# FloppyController_dsPIC.net
KiCad netlist of a schematic drawn in EAGLE
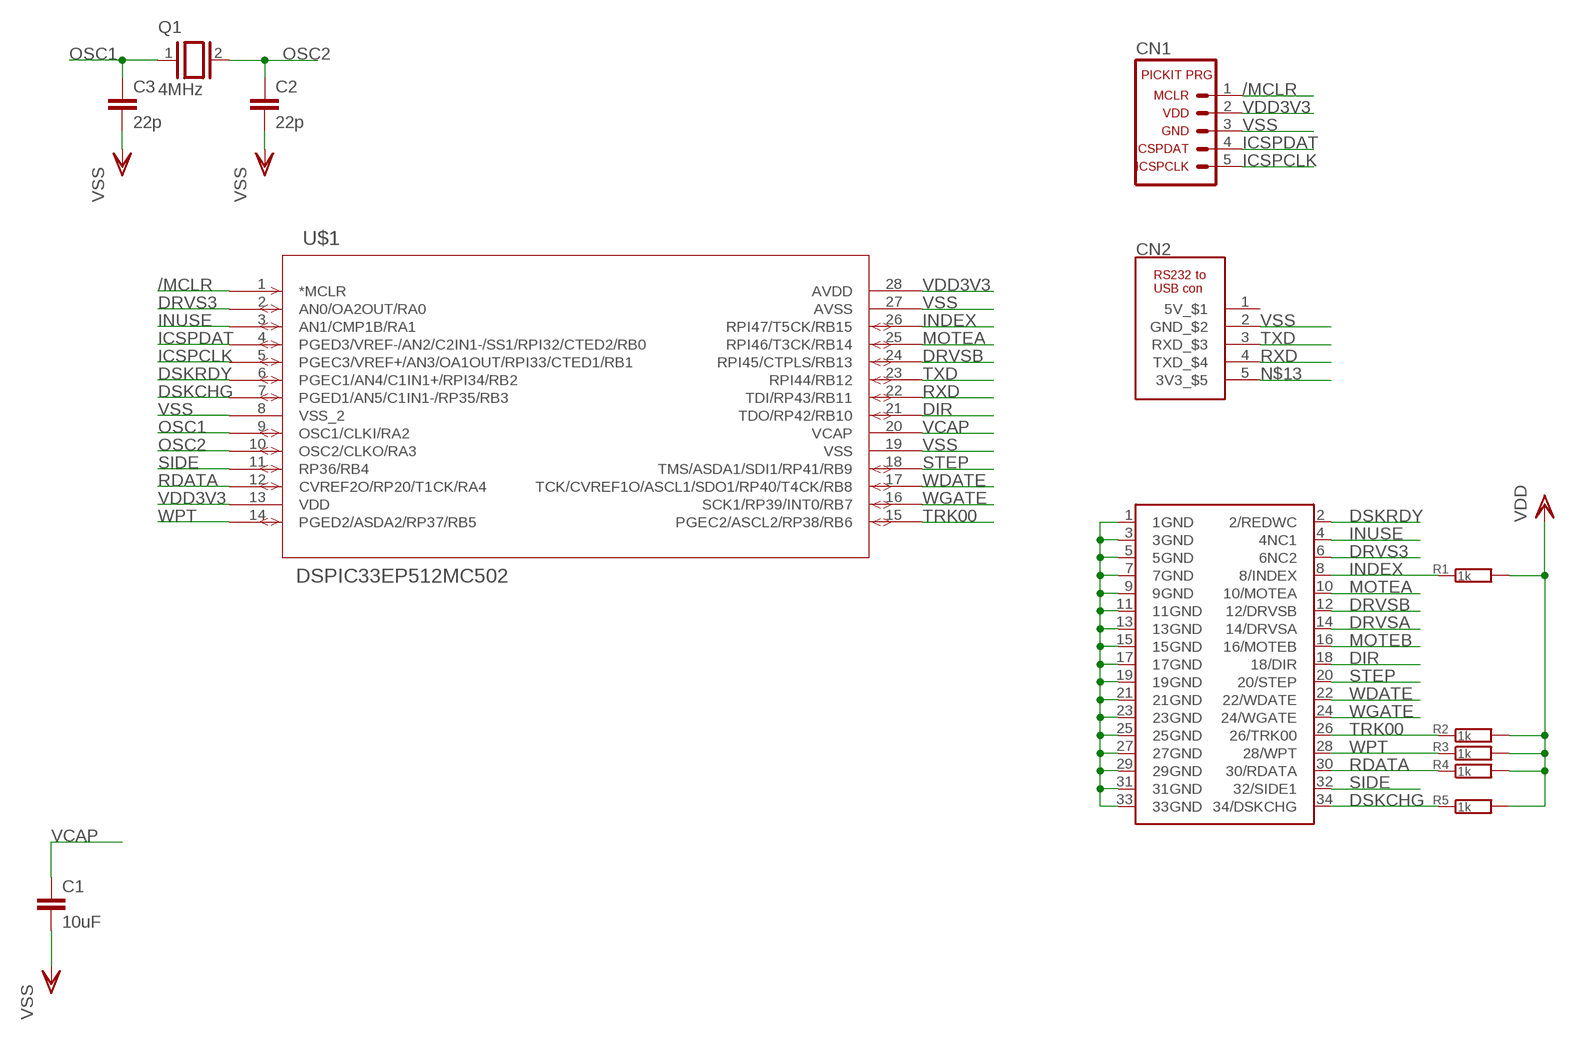
[diagram p0: schematic, sheet 1]

(export (version "E")
  (design (tool "Eeschema 10.0.6"))
  (components
    (comp (ref "C1")
      (value "10uF")
      (footprint "eagle-import:C0805TOP")
      (libsource (lib "eagle-import") (part "C-EUC0805BOTTOM"))
    )
    (comp (ref "C2")
      (value "22p")
      (footprint "eagle-import:C0603")
      (libsource (lib "eagle-import") (part "C-EUC0603"))
    )
    (comp (ref "C3")
      (value "22p")
      (footprint "eagle-import:C0603")
      (libsource (lib "eagle-import") (part "C-EUC0603"))
    )
    (comp (ref "CN1")
      (value "PICKIT3CONNECTOR")
      (footprint "eagle-import:05P")
      (libsource (lib "eagle-import") (part "PICKIT3CONNECTOR"))
    )
    (comp (ref "CN2")
      (value "RS232_TO_USB_CONNECTOR")
      (footprint "eagle-import:05P")
      (libsource (lib "eagle-import") (part "RS232_TO_USB_CONNECTOR"))
    )
    (comp (ref "Q1")
      (value "4MHz")
      (footprint "eagle-import:QS")
      (libsource (lib "eagle-import") (part "XTAL/S"))
    )
    (comp (ref "R1")
      (value "1k")
      (footprint "eagle-import:M1206")
      (libsource (lib "eagle-import") (part "R-EU_M1206BOTTOM"))
    )
    (comp (ref "R2")
      (value "1k")
      (footprint "eagle-import:M1206")
      (libsource (lib "eagle-import") (part "R-EU_M1206BOTTOM"))
    )
    (comp (ref "R3")
      (value "1k")
      (footprint "eagle-import:M1206")
      (libsource (lib "eagle-import") (part "R-EU_M1206BOTTOM"))
    )
    (comp (ref "R4")
      (value "1k")
      (footprint "eagle-import:M1206")
      (libsource (lib "eagle-import") (part "R-EU_M1206BOTTOM"))
    )
    (comp (ref "R5")
      (value "1k")
      (footprint "eagle-import:M1206")
      (libsource (lib "eagle-import") (part "R-EU_M1206BOTTOM"))
    )
    (comp (ref "U$1")
      (value "DSPIC33EP512MC502")
      (footprint "eagle-import:SPDIP28_300MC")
      (libsource (lib "eagle-import") (part "DSPIC33EP512MC502"))
    )
    (comp (ref "U$2")
      (value "FLOPPY_34PIN_CONN")
      (footprint "eagle-import:FLOPPY_34PIN_DUALROW")
      (libsource (lib "eagle-import") (part "FLOPPY_34PIN_CONN"))
    )
  )
  (nets
    (net (code "1") (name "/DIR") (class "Default")
      (node (ref "U$1") (pin "21") (pinfunction "TDO/RP42/RB10_21") (pintype "bidirectional"))
      (node (ref "U$2") (pin "18") (pinfunction "18/DIR_18") (pintype "input"))
    )
    (net (code "2") (name "/DRVS3") (class "Default")
      (node (ref "U$1") (pin "2") (pinfunction "AN0/OA2OUT/RA0_2") (pintype "bidirectional"))
      (node (ref "U$2") (pin "6") (pinfunction "6NC2_6") (pintype "bidirectional"))
    )
    (net (code "3") (name "/DRVSA") (class "Default")
      (node (ref "U$2") (pin "14") (pinfunction "14/DRVSA_14") (pintype "input"))
    )
    (net (code "4") (name "/DRVSB") (class "Default")
      (node (ref "U$1") (pin "24") (pinfunction "RPI45/CTPLS/RB13_24") (pintype "bidirectional"))
      (node (ref "U$2") (pin "12") (pinfunction "12/DRVSB_12") (pintype "input"))
    )
    (net (code "5") (name "/DSKCHG") (class "Default")
      (node (ref "R5") (pin "1") (pinfunction "1_1") (pintype "passive"))
      (node (ref "U$1") (pin "7") (pinfunction "PGED1/AN5/C1IN1-/RP35/RB3_7") (pintype "bidirectional"))
      (node (ref "U$2") (pin "34") (pinfunction "34/DSKCHG_34") (pintype "output"))
    )
    (net (code "6") (name "/DSKRDY") (class "Default")
      (node (ref "U$1") (pin "6") (pinfunction "PGEC1/AN4/C1IN1+/RPI34/RB2_6") (pintype "bidirectional"))
      (node (ref "U$2") (pin "2") (pinfunction "2/REDWC_2") (pintype "input"))
    )
    (net (code "7") (name "/ICSPCLK") (class "Default")
      (node (ref "CN1") (pin "5") (pinfunction "5_ICSPCLK_5") (pintype "passive"))
      (node (ref "U$1") (pin "5") (pinfunction "PGEC3/VREF+/AN3/OA1OUT/RPI33/CTED1/RB1_5") (pintype "bidirectional"))
    )
    (net (code "8") (name "/ICSPDAT") (class "Default")
      (node (ref "CN1") (pin "4") (pinfunction "4_ICSPDAT_4") (pintype "passive"))
      (node (ref "U$1") (pin "4") (pinfunction "PGED3/VREF-/AN2/C2IN1-/SS1/RPI32/CTED2/RB0_4") (pintype "bidirectional"))
    )
    (net (code "9") (name "/INDEX") (class "Default")
      (node (ref "R1") (pin "1") (pinfunction "1_1") (pintype "passive"))
      (node (ref "U$1") (pin "26") (pinfunction "RPI47/T5CK/RB15_26") (pintype "bidirectional"))
      (node (ref "U$2") (pin "8") (pinfunction "8/INDEX_8") (pintype "output"))
    )
    (net (code "10") (name "/INUSE") (class "Default")
      (node (ref "U$1") (pin "3") (pinfunction "AN1/CMP1B/RA1_3") (pintype "bidirectional"))
      (node (ref "U$2") (pin "4") (pinfunction "4NC1_4") (pintype "bidirectional"))
    )
    (net (code "11") (name "/MOTEA") (class "Default")
      (node (ref "U$1") (pin "25") (pinfunction "RPI46/T3CK/RB14_25") (pintype "bidirectional"))
      (node (ref "U$2") (pin "10") (pinfunction "10/MOTEA_10") (pintype "input"))
    )
    (net (code "12") (name "/MOTEB") (class "Default")
      (node (ref "U$2") (pin "16") (pinfunction "16/MOTEB_16") (pintype "input"))
    )
    (net (code "13") (name "/N$13") (class "Default")
      (node (ref "CN2") (pin "5") (pinfunction "3V3_$5_5") (pintype "bidirectional"))
    )
    (net (code "14") (name "/OSC1") (class "Default")
      (node (ref "C3") (pin "1") (pinfunction "1_1") (pintype "passive"))
      (node (ref "Q1") (pin "1") (pinfunction "1_1") (pintype "passive"))
      (node (ref "U$1") (pin "9") (pinfunction "OSC1/CLKI/RA2_9") (pintype "bidirectional"))
    )
    (net (code "15") (name "/OSC2") (class "Default")
      (node (ref "C2") (pin "1") (pinfunction "1_1") (pintype "passive"))
      (node (ref "Q1") (pin "2") (pinfunction "2_2") (pintype "passive"))
      (node (ref "U$1") (pin "10") (pinfunction "OSC2/CLKO/RA3_10") (pintype "bidirectional"))
    )
    (net (code "16") (name "/RDATA") (class "Default")
      (node (ref "R4") (pin "1") (pinfunction "1_1") (pintype "passive"))
      (node (ref "U$1") (pin "12") (pinfunction "CVREF2O/RP20/T1CK/RA4_12") (pintype "bidirectional"))
      (node (ref "U$2") (pin "30") (pinfunction "30/RDATA_30") (pintype "output"))
    )
    (net (code "17") (name "/RXD") (class "Default")
      (node (ref "CN2") (pin "4") (pinfunction "TXD_$4_4") (pintype "bidirectional"))
      (node (ref "U$1") (pin "22") (pinfunction "TDI/RP43/RB11_22") (pintype "bidirectional"))
    )
    (net (code "18") (name "/SIDE") (class "Default")
      (node (ref "U$1") (pin "11") (pinfunction "RP36/RB4_11") (pintype "bidirectional"))
      (node (ref "U$2") (pin "32") (pinfunction "32/SIDE1_32") (pintype "input"))
    )
    (net (code "19") (name "/STEP") (class "Default")
      (node (ref "U$1") (pin "18") (pinfunction "TMS/ASDA1/SDI1/RP41/RB9_18") (pintype "bidirectional"))
      (node (ref "U$2") (pin "20") (pinfunction "20/STEP_20") (pintype "input"))
    )
    (net (code "20") (name "/TRK00") (class "Default")
      (node (ref "R2") (pin "1") (pinfunction "1_1") (pintype "passive"))
      (node (ref "U$1") (pin "15") (pinfunction "PGEC2/ASCL2/RP38/RB6_15") (pintype "bidirectional"))
      (node (ref "U$2") (pin "26") (pinfunction "26/TRK00_26") (pintype "output"))
    )
    (net (code "21") (name "/TXD") (class "Default")
      (node (ref "CN2") (pin "3") (pinfunction "RXD_$3_3") (pintype "bidirectional"))
      (node (ref "U$1") (pin "23") (pinfunction "RPI44/RB12_23") (pintype "bidirectional"))
    )
    (net (code "22") (name "/VCAP") (class "Default")
      (node (ref "C1") (pin "1") (pinfunction "1_1") (pintype "passive"))
      (node (ref "U$1") (pin "20") (pinfunction "VCAP_20") (pintype "power_in"))
    )
    (net (code "23") (name "/VDD3V3") (class "Default")
      (node (ref "CN1") (pin "2") (pinfunction "2_VDD_2") (pintype "passive"))
      (node (ref "U$1") (pin "13") (pinfunction "VDD_13") (pintype "power_in"))
      (node (ref "U$1") (pin "28") (pinfunction "AVDD_28") (pintype "power_in"))
    )
    (net (code "24") (name "/WDATE") (class "Default")
      (node (ref "U$1") (pin "17") (pinfunction "TCK/CVREF1O/ASCL1/SDO1/RP40/T4CK/RB8_17") (pintype "bidirectional"))
      (node (ref "U$2") (pin "22") (pinfunction "22/WDATE_22") (pintype "input"))
    )
    (net (code "25") (name "/WGATE") (class "Default")
      (node (ref "U$1") (pin "16") (pinfunction "SCK1/RP39/INT0/RB7_16") (pintype "bidirectional"))
      (node (ref "U$2") (pin "24") (pinfunction "24/WGATE_24") (pintype "input"))
    )
    (net (code "26") (name "/WPT") (class "Default")
      (node (ref "R3") (pin "1") (pinfunction "1_1") (pintype "passive"))
      (node (ref "U$1") (pin "14") (pinfunction "PGED2/ASDA2/RP37/RB5_14") (pintype "bidirectional"))
      (node (ref "U$2") (pin "28") (pinfunction "28/WPT_28") (pintype "output"))
    )
    (net (code "27") (name "/{slash}MCLR") (class "Default")
      (node (ref "CN1") (pin "1") (pinfunction "1_MCLR_1") (pintype "passive"))
      (node (ref "U$1") (pin "1") (pinfunction "*MCLR_1") (pintype "input"))
    )
    (net (code "28") (name "Net-(U$2-11GND)") (class "Default")
      (node (ref "U$2") (pin "1") (pinfunction "1GND_1") (pintype "power_in"))
      (node (ref "U$2") (pin "11") (pinfunction "11GND_11") (pintype "power_in"))
      (node (ref "U$2") (pin "13") (pinfunction "13GND_13") (pintype "power_in"))
      (node (ref "U$2") (pin "15") (pinfunction "15GND_15") (pintype "power_in"))
      (node (ref "U$2") (pin "17") (pinfunction "17GND_17") (pintype "power_in"))
      (node (ref "U$2") (pin "19") (pinfunction "19GND_19") (pintype "power_in"))
      (node (ref "U$2") (pin "21") (pinfunction "21GND_21") (pintype "power_in"))
      (node (ref "U$2") (pin "23") (pinfunction "23GND_23") (pintype "power_in"))
      (node (ref "U$2") (pin "25") (pinfunction "25GND_25") (pintype "power_in"))
      (node (ref "U$2") (pin "27") (pinfunction "27GND_27") (pintype "power_in"))
      (node (ref "U$2") (pin "29") (pinfunction "29GND_29") (pintype "power_in"))
      (node (ref "U$2") (pin "3") (pinfunction "3GND_3") (pintype "power_in"))
      (node (ref "U$2") (pin "31") (pinfunction "31GND_31") (pintype "power_in"))
      (node (ref "U$2") (pin "33") (pinfunction "33GND_33") (pintype "power_in"))
      (node (ref "U$2") (pin "5") (pinfunction "5GND_5") (pintype "power_in"))
      (node (ref "U$2") (pin "7") (pinfunction "7GND_7") (pintype "power_in"))
      (node (ref "U$2") (pin "9") (pinfunction "9GND_9") (pintype "power_in"))
    )
    (net (code "29") (name "VDD") (class "Default")
      (node (ref "R1") (pin "2") (pinfunction "2_2") (pintype "passive"))
      (node (ref "R2") (pin "2") (pinfunction "2_2") (pintype "passive"))
      (node (ref "R3") (pin "2") (pinfunction "2_2") (pintype "passive"))
      (node (ref "R4") (pin "2") (pinfunction "2_2") (pintype "passive"))
      (node (ref "R5") (pin "2") (pinfunction "2_2") (pintype "passive"))
    )
    (net (code "30") (name "VSS") (class "Default")
      (node (ref "C1") (pin "2") (pinfunction "2_2") (pintype "passive"))
      (node (ref "C2") (pin "2") (pinfunction "2_2") (pintype "passive"))
      (node (ref "C3") (pin "2") (pinfunction "2_2") (pintype "passive"))
      (node (ref "CN1") (pin "3") (pinfunction "3_GND_3") (pintype "passive"))
      (node (ref "CN2") (pin "2") (pinfunction "GND_$2_2") (pintype "bidirectional"))
      (node (ref "U$1") (pin "19") (pinfunction "VSS_19") (pintype "power_in"))
      (node (ref "U$1") (pin "27") (pinfunction "AVSS_27") (pintype "power_in"))
      (node (ref "U$1") (pin "8") (pinfunction "VSS_2_8") (pintype "power_in"))
    )
    (net (code "31") (name "unconnected-(CN2-5V_$1-Pad1)") (class "Default")
      (node (ref "CN2") (pin "1") (pinfunction "5V_$1_1") (pintype "bidirectional"))
    )
  )
)
